# resolver.net
KiCad netlist of a schematic drawn in EAGLE
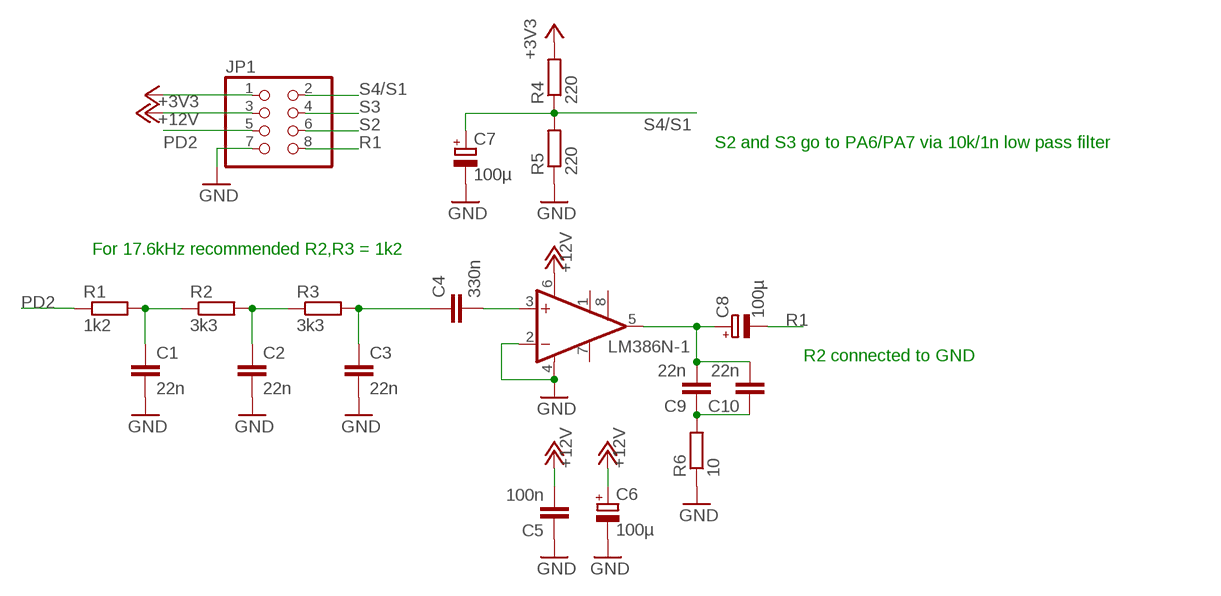
[diagram p0: schematic, sheet 1]

(export (version "E")
  (design (tool "Eeschema 10.0.6"))
  (components
    (comp (ref "C1")
      (value "22n")
      (footprint "eagle-import:C050-024X044")
      (libsource (lib "eagle-import") (part "C-EU050-024X044"))
    )
    (comp (ref "C2")
      (value "22n")
      (footprint "eagle-import:C050-024X044")
      (libsource (lib "eagle-import") (part "C-EU050-024X044"))
    )
    (comp (ref "C3")
      (value "22n")
      (footprint "eagle-import:C050-024X044")
      (libsource (lib "eagle-import") (part "C-EU050-024X044"))
    )
    (comp (ref "C4")
      (value "330n")
      (footprint "eagle-import:C025-024X044")
      (libsource (lib "eagle-import") (part "C-EU025-024X044"))
    )
    (comp (ref "C5")
      (value "100n")
      (footprint "eagle-import:C025-024X044")
      (libsource (lib "eagle-import") (part "C-EU025-024X044"))
    )
    (comp (ref "C6")
      (value "100µ")
      (footprint "eagle-import:E2,5-6E")
      (libsource (lib "eagle-import") (part "CPOL-EUE2,5-6E"))
    )
    (comp (ref "C7")
      (value "100µ")
      (footprint "eagle-import:E2,5-6E")
      (libsource (lib "eagle-import") (part "CPOL-EUE2,5-6E"))
    )
    (comp (ref "C8")
      (value "100µ")
      (footprint "eagle-import:E2,5-6E")
      (libsource (lib "eagle-import") (part "CPOL-EUE2,5-6E"))
    )
    (comp (ref "C9")
      (value "22n")
      (footprint "eagle-import:C050-024X044")
      (libsource (lib "eagle-import") (part "C-EU050-024X044"))
    )
    (comp (ref "C10")
      (value "22n")
      (footprint "eagle-import:C050-024X044")
      (libsource (lib "eagle-import") (part "C-EU050-024X044"))
    )
    (comp (ref "IC1")
      (value "LM386N-1")
      (footprint "eagle-import:DIL08")
      (libsource (lib "eagle-import") (part "LM386?-N1"))
    )
    (comp (ref "JP1")
      (value "PINHD-2X4")
      (footprint "eagle-import:2X04")
      (libsource (lib "eagle-import") (part "PINHD-2X4"))
    )
    (comp (ref "R1")
      (value "1k2")
      (footprint "eagle-import:0204V")
      (libsource (lib "eagle-import") (part "R-EU_0204/2V"))
    )
    (comp (ref "R2")
      (value "3k3")
      (footprint "eagle-import:0204V")
      (libsource (lib "eagle-import") (part "R-EU_0204/2V"))
    )
    (comp (ref "R3")
      (value "3k3")
      (footprint "eagle-import:0204V")
      (libsource (lib "eagle-import") (part "R-EU_0204/2V"))
    )
    (comp (ref "R4")
      (value "220")
      (footprint "eagle-import:0207_10")
      (libsource (lib "eagle-import") (part "R-EU_0207/10"))
    )
    (comp (ref "R5")
      (value "220")
      (footprint "eagle-import:0204V")
      (libsource (lib "eagle-import") (part "R-EU_0204/2V"))
    )
    (comp (ref "R6")
      (value "10")
      (footprint "eagle-import:0204V")
      (libsource (lib "eagle-import") (part "R-EU_0204/2V"))
    )
  )
  (nets
    (net (code "1") (name "+3V3") (class "Default")
      (node (ref "JP1") (pin "1") (pinfunction "1_1") (pintype "passive"))
      (node (ref "R4") (pin "2") (pinfunction "2_2") (pintype "passive"))
    )
    (net (code "2") (name "+12V") (class "Default")
      (node (ref "C5") (pin "2") (pinfunction "2_2") (pintype "passive"))
      (node (ref "C6") (pin "+") (pinfunction "+_+") (pintype "passive"))
      (node (ref "IC1") (pin "6") (pinfunction "VS_6") (pintype "power_in"))
      (node (ref "JP1") (pin "3") (pinfunction "3_3") (pintype "passive"))
    )
    (net (code "3") (name "/PD2") (class "Default")
      (node (ref "JP1") (pin "5") (pinfunction "5_5") (pintype "passive"))
      (node (ref "R1") (pin "1") (pinfunction "1_1") (pintype "passive"))
    )
    (net (code "4") (name "/R1") (class "Default")
      (node (ref "C8") (pin "-") (pinfunction "-_-") (pintype "passive"))
      (node (ref "JP1") (pin "8") (pinfunction "8_8") (pintype "passive"))
    )
    (net (code "5") (name "/S2") (class "Default")
      (node (ref "JP1") (pin "6") (pinfunction "6_6") (pintype "passive"))
    )
    (net (code "6") (name "/S3") (class "Default")
      (node (ref "JP1") (pin "4") (pinfunction "4_4") (pintype "passive"))
    )
    (net (code "7") (name "/S4{slash}S1") (class "Default")
      (node (ref "C7") (pin "+") (pinfunction "+_+") (pintype "passive"))
      (node (ref "JP1") (pin "2") (pinfunction "2_2") (pintype "passive"))
      (node (ref "R4") (pin "1") (pinfunction "1_1") (pintype "passive"))
      (node (ref "R5") (pin "2") (pinfunction "2_2") (pintype "passive"))
    )
    (net (code "8") (name "GND") (class "Default")
      (node (ref "C1") (pin "2") (pinfunction "2_2") (pintype "passive"))
      (node (ref "C2") (pin "2") (pinfunction "2_2") (pintype "passive"))
      (node (ref "C3") (pin "2") (pinfunction "2_2") (pintype "passive"))
      (node (ref "C5") (pin "1") (pinfunction "1_1") (pintype "passive"))
      (node (ref "C6") (pin "-") (pinfunction "-_-") (pintype "passive"))
      (node (ref "C7") (pin "-") (pinfunction "-_-") (pintype "passive"))
      (node (ref "IC1") (pin "2") (pinfunction "-IN_2") (pintype "input"))
      (node (ref "IC1") (pin "4") (pinfunction "GND_4") (pintype "power_in"))
      (node (ref "JP1") (pin "7") (pinfunction "7_7") (pintype "passive"))
      (node (ref "R5") (pin "1") (pinfunction "1_1") (pintype "passive"))
      (node (ref "R6") (pin "1") (pinfunction "1_1") (pintype "passive"))
    )
    (net (code "9") (name "Net-(C1-Pad1)") (class "Default")
      (node (ref "C1") (pin "1") (pinfunction "1_1") (pintype "passive"))
      (node (ref "R1") (pin "2") (pinfunction "2_2") (pintype "passive"))
      (node (ref "R2") (pin "1") (pinfunction "1_1") (pintype "passive"))
    )
    (net (code "10") (name "Net-(C2-Pad1)") (class "Default")
      (node (ref "C2") (pin "1") (pinfunction "1_1") (pintype "passive"))
      (node (ref "R2") (pin "2") (pinfunction "2_2") (pintype "passive"))
      (node (ref "R3") (pin "1") (pinfunction "1_1") (pintype "passive"))
    )
    (net (code "11") (name "Net-(C3-Pad1)") (class "Default")
      (node (ref "C3") (pin "1") (pinfunction "1_1") (pintype "passive"))
      (node (ref "C4") (pin "1") (pinfunction "1_1") (pintype "passive"))
      (node (ref "R3") (pin "2") (pinfunction "2_2") (pintype "passive"))
    )
    (net (code "12") (name "Net-(C10-Pad1)") (class "Default")
      (node (ref "C10") (pin "1") (pinfunction "1_1") (pintype "passive"))
      (node (ref "C9") (pin "1") (pinfunction "1_1") (pintype "passive"))
      (node (ref "R6") (pin "2") (pinfunction "2_2") (pintype "passive"))
    )
    (net (code "13") (name "Net-(IC1-+IN)") (class "Default")
      (node (ref "C4") (pin "2") (pinfunction "2_2") (pintype "passive"))
      (node (ref "IC1") (pin "3") (pinfunction "+IN_3") (pintype "input"))
    )
    (net (code "14") (name "Net-(IC1-OUT)") (class "Default")
      (node (ref "C10") (pin "2") (pinfunction "2_2") (pintype "passive"))
      (node (ref "C8") (pin "+") (pinfunction "+_+") (pintype "passive"))
      (node (ref "C9") (pin "2") (pinfunction "2_2") (pintype "passive"))
      (node (ref "IC1") (pin "5") (pinfunction "OUT_5") (pintype "output"))
    )
    (net (code "15") (name "unconnected-(IC1-BYPASS-Pad7)") (class "Default")
      (node (ref "IC1") (pin "7") (pinfunction "BYPASS_7") (pintype "passive"))
    )
    (net (code "16") (name "unconnected-(IC1-GAIN-Pad1)") (class "Default")
      (node (ref "IC1") (pin "1") (pinfunction "GAIN_1") (pintype "passive"))
    )
    (net (code "17") (name "unconnected-(IC1-GAIN-Pad8)") (class "Default")
      (node (ref "IC1") (pin "8") (pinfunction "GAIN_8") (pintype "passive"))
    )
  )
)
